# BOARD-connector.net
KiCad netlist of a schematic drawn in Altium Designer
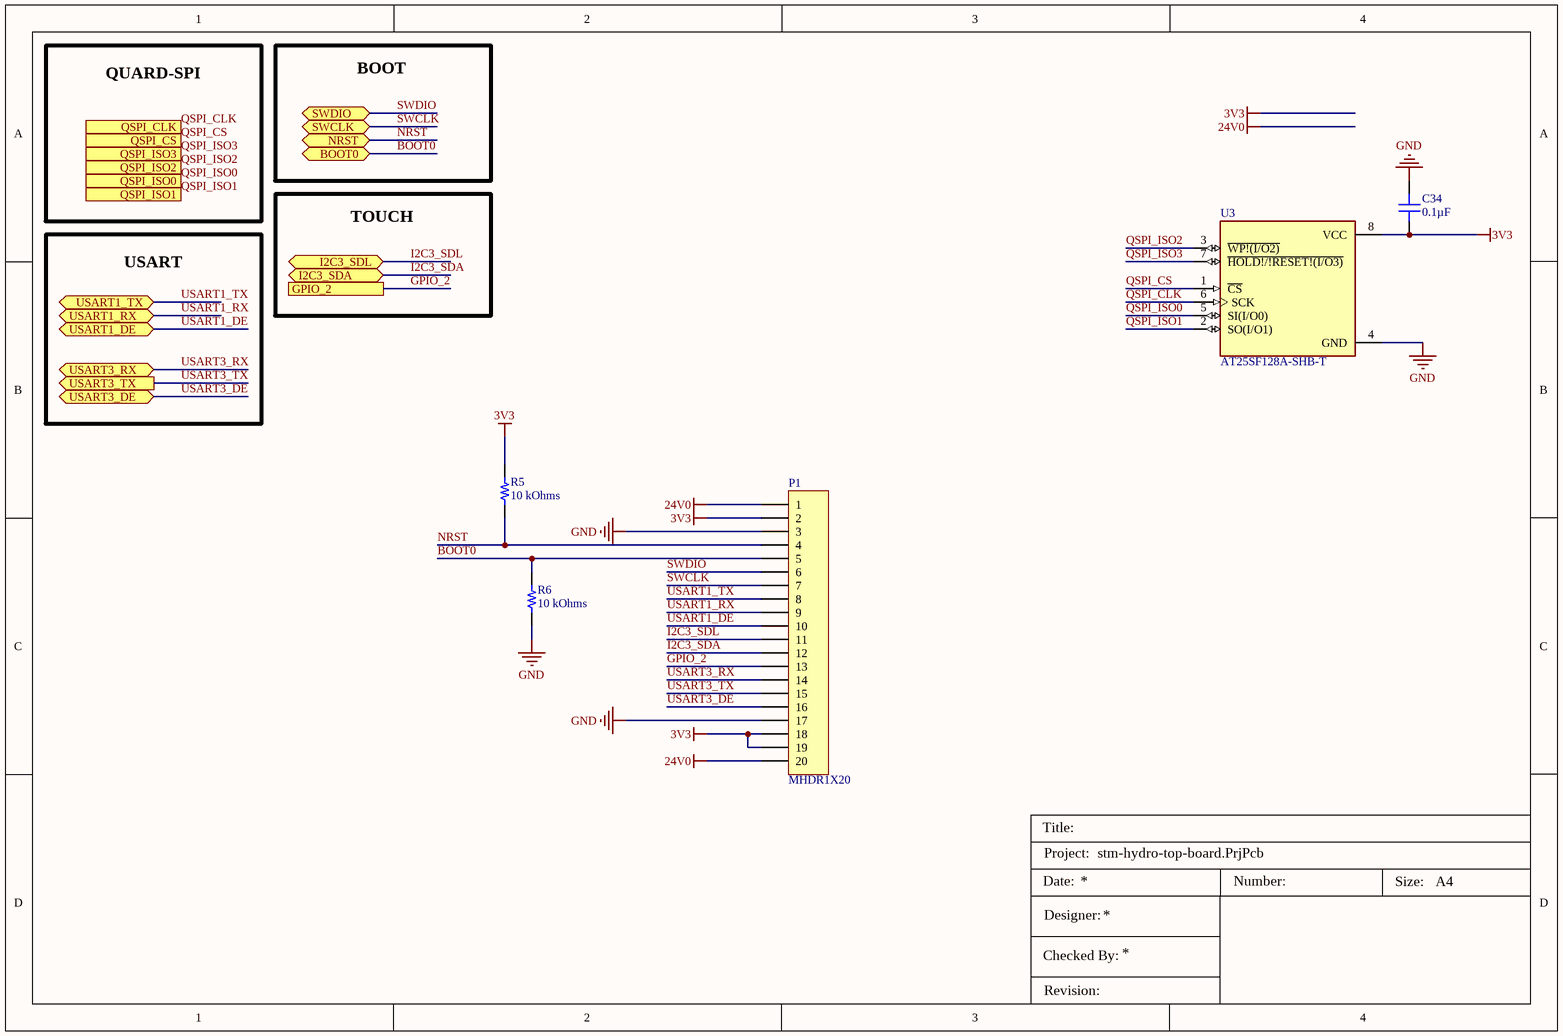
[diagram p0: BOARD-connector.SchDoc]

(export (version "E")
  (design (tool "Eeschema 10.0.6"))
  (components
    (comp (ref "C34")
      (value "0.1µF")
      (footprint "CAP 0603_1608")
      (description "CAP CER 0.1UF 6.3V X7R 0603")
      (fields (field (name "PART NUMBER") "6R3X14W104MV4T"))
      (libsource (lib "Celestial Altium Library - altium_library") (part "Capacitor"))
    )
    (comp (ref "P1")
      (value "MHDR1X20")
      (footprint "MHDR1X20")
      (description "Header, 20-Pin")
      (fields (field (name "PUBLISHER") "Altium Limited"))
      (libsource (lib "Miscellaneous Connectors") (part "MHDR1X20"))
    )
    (comp (ref "R5")
      (value "10 kOhms")
      (footprint "RES 0603_1608")
      (description "RES SMD 10K OHM 1% 1/4W 0603")
      (fields (field (name "PART NUMBER") "CRCW060310K0FKEAHP"))
      (libsource (lib "Celestial Altium Library - altium_library") (part "Resistor"))
    )
    (comp (ref "R6")
      (value "10 kOhms")
      (footprint "RES 0603_1608")
      (description "RES SMD 10K OHM 1% 1/4W 0603")
      (fields (field (name "PART NUMBER") "CRCW060310K0FKEAHP"))
      (libsource (lib "Celestial Altium Library - altium_library") (part "Resistor"))
    )
    (comp (ref "U3")
      (value "AT25SF128A-SHB-T")
      (footprint "PcbLib1:SOIC127P790X216-8N")
      (description "128 Mbit Serial NOR Flash Memory with Dual and Quad I/O Support")
      (fields (field (name "MF") "Dialog Semiconductor"))
      (libsource (lib "Schlib1") (part "AT25SF128A-SHB-T"))
    )
  )
  (nets
    (net (code "1") (name "/BOOT0") (class "Default")
      (node (ref "P1") (pin "5") (pinfunction "5_5") (pintype "passive"))
      (node (ref "R6") (pin "2") (pinfunction "2_2") (pintype "passive"))
    )
    (net (code "2") (name "/GPIO_2") (class "Default")
      (node (ref "P1") (pin "13") (pinfunction "13_13") (pintype "passive"))
    )
    (net (code "3") (name "/I2C3_SDA") (class "Default")
      (node (ref "P1") (pin "12") (pinfunction "12_12") (pintype "passive"))
    )
    (net (code "4") (name "/I2C3_SDL") (class "Default")
      (node (ref "P1") (pin "11") (pinfunction "11_11") (pintype "passive"))
    )
    (net (code "5") (name "/NRST") (class "Default")
      (node (ref "P1") (pin "4") (pinfunction "4_4") (pintype "passive"))
      (node (ref "R5") (pin "1") (pinfunction "1_1") (pintype "passive"))
    )
    (net (code "6") (name "/QSPI_CLK") (class "Default")
      (node (ref "U3") (pin "6") (pinfunction "SCK_6") (pintype "input"))
    )
    (net (code "7") (name "/QSPI_CS") (class "Default")
      (node (ref "U3") (pin "1") (pinfunction "~{CS}_1") (pintype "input"))
    )
    (net (code "8") (name "/QSPI_ISO0") (class "Default")
      (node (ref "U3") (pin "5") (pinfunction "SI(I/O0)_5") (pintype "bidirectional"))
    )
    (net (code "9") (name "/QSPI_ISO1") (class "Default")
      (node (ref "U3") (pin "2") (pinfunction "SO(I/O1)_2") (pintype "bidirectional"))
    )
    (net (code "10") (name "/QSPI_ISO2") (class "Default")
      (node (ref "U3") (pin "3") (pinfunction "~{WP!(I/O2)}_3") (pintype "bidirectional"))
    )
    (net (code "11") (name "/QSPI_ISO3") (class "Default")
      (node (ref "U3") (pin "7") (pinfunction "~{HOLD!/!RESET!(I/O3)}_7") (pintype "bidirectional"))
    )
    (net (code "12") (name "/SWCLK") (class "Default")
      (node (ref "P1") (pin "7") (pinfunction "7_7") (pintype "passive"))
    )
    (net (code "13") (name "/SWDIO") (class "Default")
      (node (ref "P1") (pin "6") (pinfunction "6_6") (pintype "passive"))
    )
    (net (code "14") (name "/USART1_DE") (class "Default")
      (node (ref "P1") (pin "10") (pinfunction "10_10") (pintype "passive"))
    )
    (net (code "15") (name "/USART1_RX") (class "Default")
      (node (ref "P1") (pin "9") (pinfunction "9_9") (pintype "passive"))
    )
    (net (code "16") (name "/USART1_TX") (class "Default")
      (node (ref "P1") (pin "8") (pinfunction "8_8") (pintype "passive"))
    )
    (net (code "17") (name "/USART3_DE") (class "Default")
      (node (ref "P1") (pin "16") (pinfunction "16_16") (pintype "passive"))
    )
    (net (code "18") (name "/USART3_RX") (class "Default")
      (node (ref "P1") (pin "14") (pinfunction "14_14") (pintype "passive"))
    )
    (net (code "19") (name "/USART3_TX") (class "Default")
      (node (ref "P1") (pin "15") (pinfunction "15_15") (pintype "passive"))
    )
    (net (code "20") (name "3V3") (class "Default")
      (node (ref "C34") (pin "1") (pinfunction "1_1") (pintype "passive"))
      (node (ref "P1") (pin "18") (pinfunction "18_18") (pintype "passive"))
      (node (ref "P1") (pin "19") (pinfunction "19_19") (pintype "passive"))
      (node (ref "P1") (pin "2") (pinfunction "2_2") (pintype "passive"))
      (node (ref "R5") (pin "2") (pinfunction "2_2") (pintype "passive"))
      (node (ref "U3") (pin "8") (pinfunction "VCC_8") (pintype "power_in"))
    )
    (net (code "21") (name "24V0") (class "Default")
      (node (ref "P1") (pin "1") (pinfunction "1_1") (pintype "passive"))
      (node (ref "P1") (pin "20") (pinfunction "20_20") (pintype "passive"))
    )
    (net (code "22") (name "GND") (class "Default")
      (node (ref "C34") (pin "2") (pinfunction "2_2") (pintype "passive"))
      (node (ref "P1") (pin "17") (pinfunction "17_17") (pintype "passive"))
      (node (ref "P1") (pin "3") (pinfunction "3_3") (pintype "passive"))
      (node (ref "R6") (pin "1") (pinfunction "1_1") (pintype "passive"))
      (node (ref "U3") (pin "4") (pinfunction "GND_4") (pintype "power_in"))
    )
  )
)
